# analog_in.net
KiCad netlist of a schematic drawn in Altium Designer
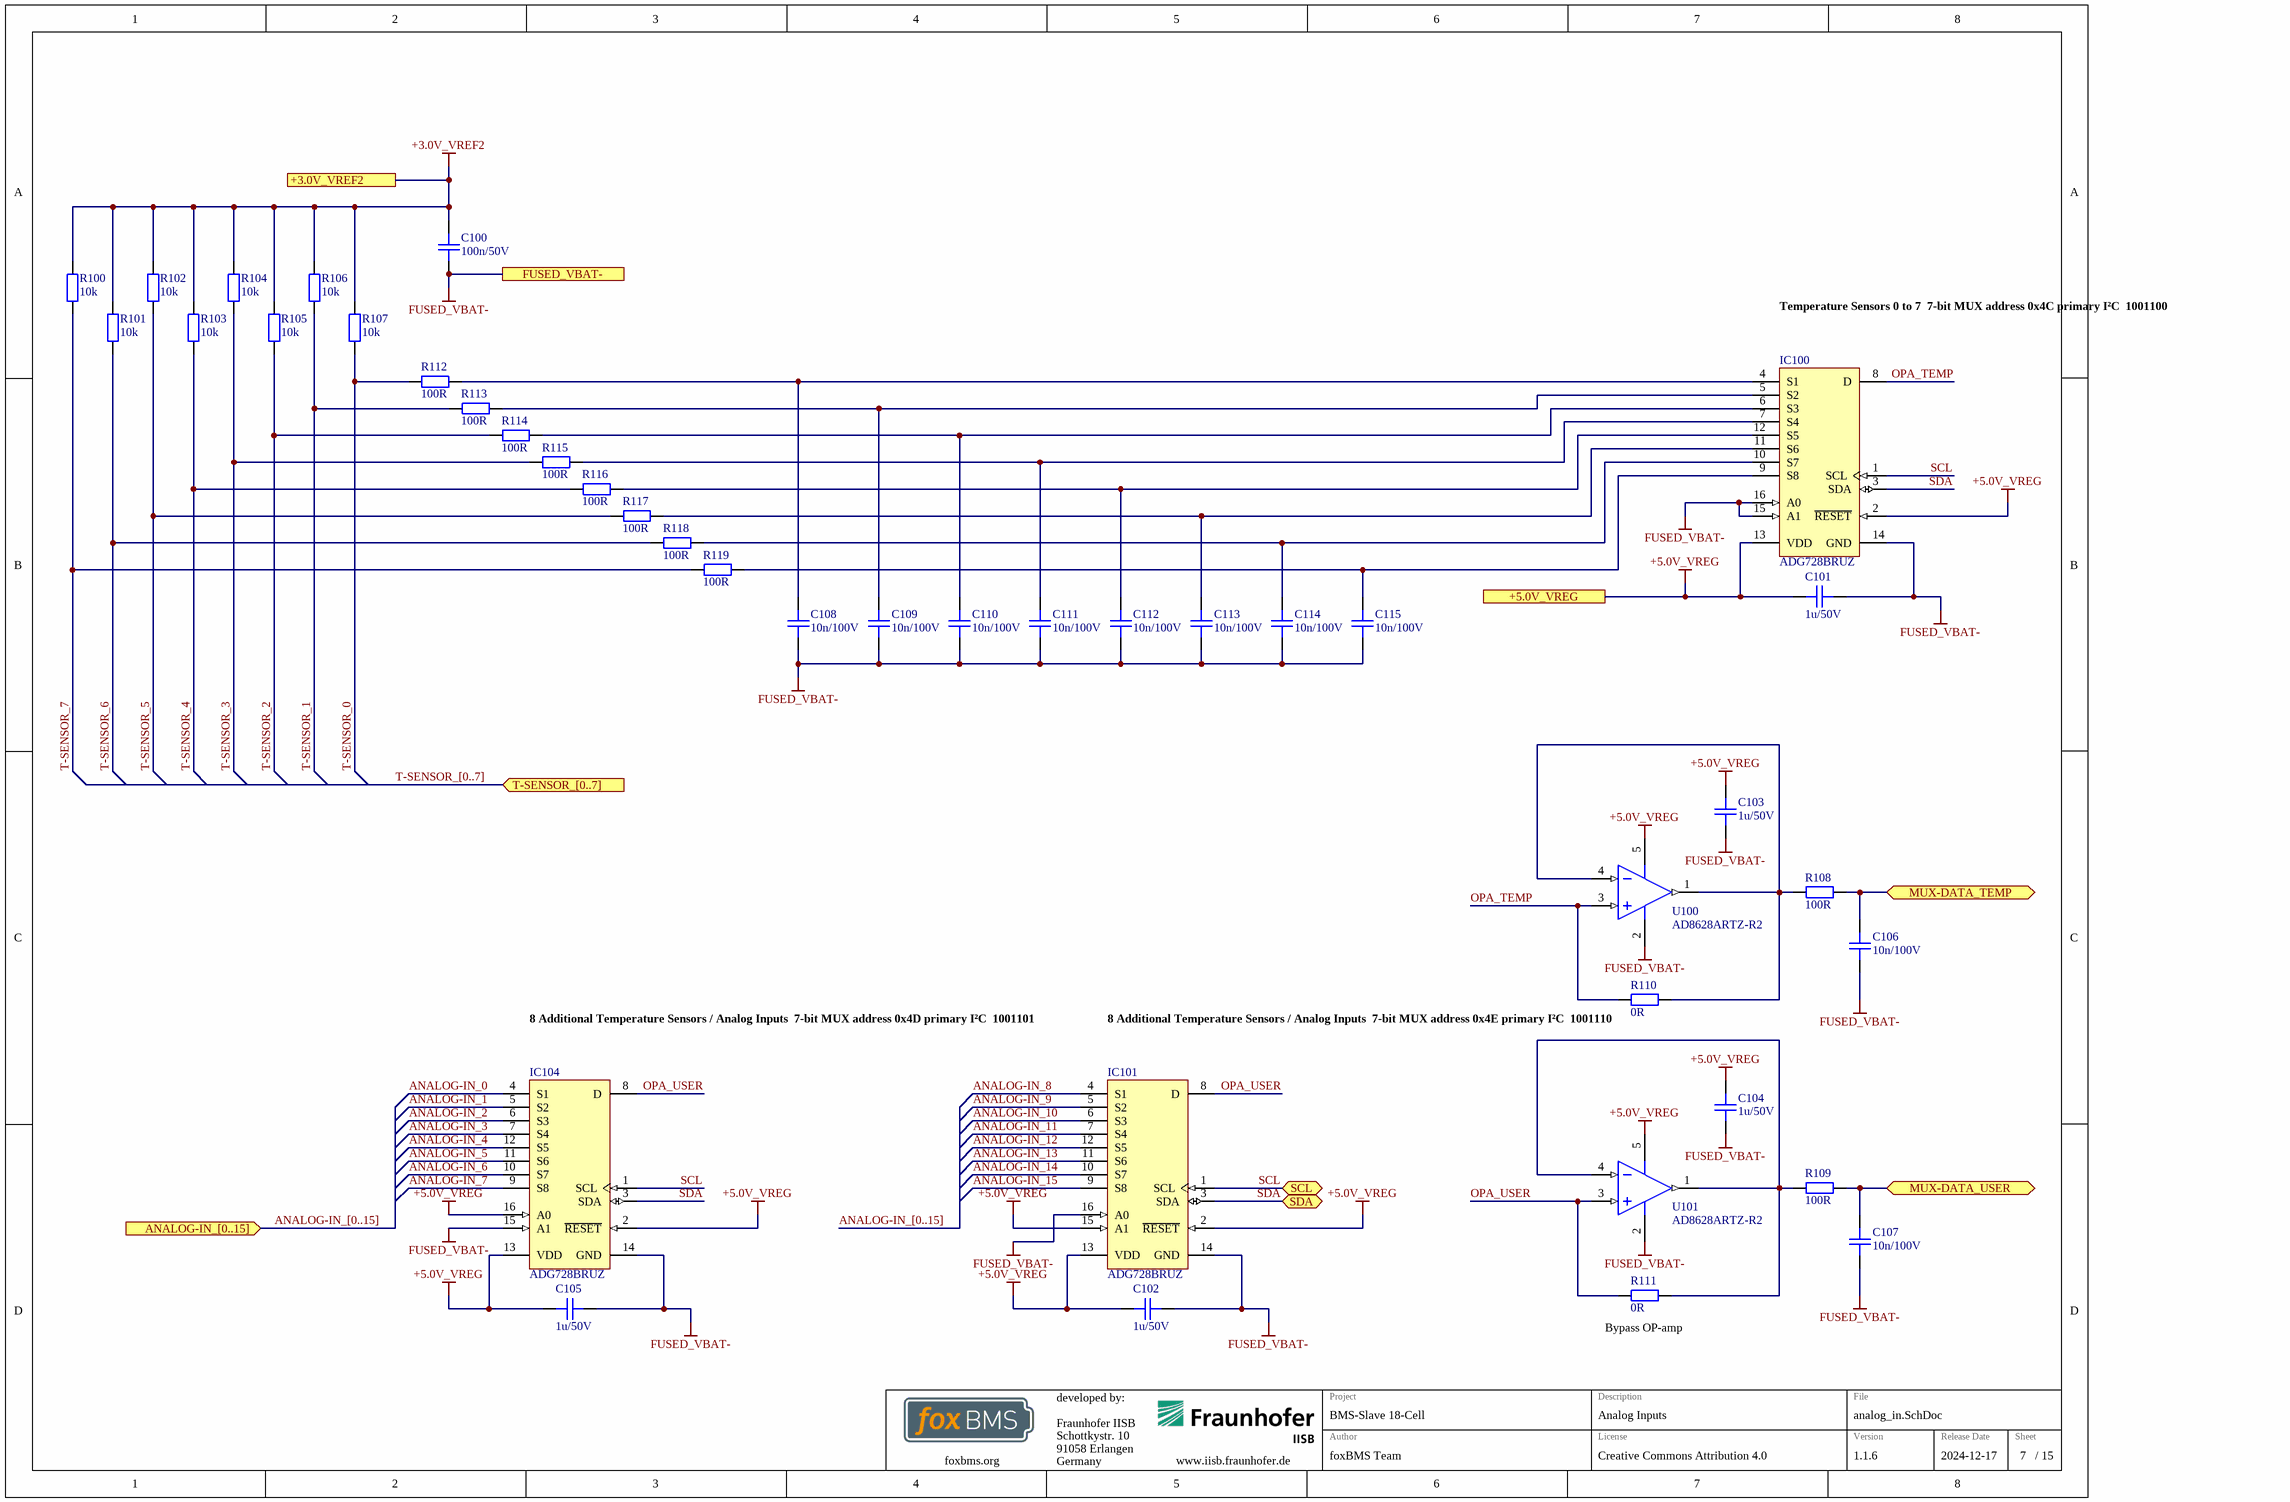
[diagram p0: analog_in.SchDoc]

(export (version "E")
  (design (tool "Eeschema 10.0.6"))
  (components
    (comp (ref "C100")
      (value "100n/50V")
      (footprint "CAPC1608X08N")
      (description "MLCC")
      (fields (field (name "PART NUMBER") "gen_C_ceramic_100n_50V_X7R_0603"))
      (libsource (lib "OE750") (part "C"))
    )
    (comp (ref "C101")
      (value "1u/50V")
      (footprint "CAPC2012X14N")
      (description "MLCC")
      (fields (field (name "PART NUMBER") "gen_C_ceramic_1u_50V_X7R_0805") (field (name "TOLERANCE") "± 10%"))
      (libsource (lib "OE750") (part "C"))
    )
    (comp (ref "C102")
      (value "1u/50V")
      (footprint "CAPC2012X14N")
      (description "MLCC")
      (fields (field (name "PART NUMBER") "gen_C_ceramic_1u_50V_X7R_0805") (field (name "TOLERANCE") "± 10%"))
      (libsource (lib "OE750") (part "C"))
    )
    (comp (ref "C103")
      (value "1u/50V")
      (footprint "CAPC2012X14N")
      (description "MLCC")
      (fields (field (name "PART NUMBER") "gen_C_ceramic_1u_50V_X7R_0805") (field (name "TOLERANCE") "± 10%"))
      (libsource (lib "OE750") (part "C"))
    )
    (comp (ref "C104")
      (value "1u/50V")
      (footprint "CAPC2012X14N")
      (description "MLCC")
      (fields (field (name "PART NUMBER") "gen_C_ceramic_1u_50V_X7R_0805") (field (name "TOLERANCE") "± 10%"))
      (libsource (lib "OE750") (part "C"))
    )
    (comp (ref "C105")
      (value "1u/50V")
      (footprint "CAPC2012X14N")
      (description "MLCC")
      (fields (field (name "PART NUMBER") "gen_C_ceramic_1u_50V_X7R_0805") (field (name "TOLERANCE") "± 10%"))
      (libsource (lib "OE750") (part "C"))
    )
    (comp (ref "C106")
      (value "10n/100V")
      (footprint "CAPC1608X08N")
      (description "MLCC")
      (fields (field (name "PART NUMBER") "gen_C_ceramic_10n_100V_X7R_0603"))
      (libsource (lib "OE750") (part "C"))
    )
    (comp (ref "C107")
      (value "10n/100V")
      (footprint "CAPC1608X08N")
      (description "MLCC")
      (fields (field (name "PART NUMBER") "gen_C_ceramic_10n_100V_X7R_0603"))
      (libsource (lib "OE750") (part "C"))
    )
    (comp (ref "C108")
      (value "10n/100V")
      (footprint "CAPC1608X08N")
      (description "MLCC")
      (fields (field (name "PART NUMBER") "gen_C_ceramic_10n_100V_X7R_0603"))
      (libsource (lib "OE750") (part "C"))
    )
    (comp (ref "C109")
      (value "10n/100V")
      (footprint "CAPC1608X08N")
      (description "MLCC")
      (fields (field (name "PART NUMBER") "gen_C_ceramic_10n_100V_X7R_0603"))
      (libsource (lib "OE750") (part "C"))
    )
    (comp (ref "C110")
      (value "10n/100V")
      (footprint "CAPC1608X08N")
      (description "MLCC")
      (fields (field (name "PART NUMBER") "gen_C_ceramic_10n_100V_X7R_0603"))
      (libsource (lib "OE750") (part "C"))
    )
    (comp (ref "C111")
      (value "10n/100V")
      (footprint "CAPC1608X08N")
      (description "MLCC")
      (fields (field (name "PART NUMBER") "gen_C_ceramic_10n_100V_X7R_0603"))
      (libsource (lib "OE750") (part "C"))
    )
    (comp (ref "C112")
      (value "10n/100V")
      (footprint "CAPC1608X08N")
      (description "MLCC")
      (fields (field (name "PART NUMBER") "gen_C_ceramic_10n_100V_X7R_0603"))
      (libsource (lib "OE750") (part "C"))
    )
    (comp (ref "C113")
      (value "10n/100V")
      (footprint "CAPC1608X08N")
      (description "MLCC")
      (fields (field (name "PART NUMBER") "gen_C_ceramic_10n_100V_X7R_0603"))
      (libsource (lib "OE750") (part "C"))
    )
    (comp (ref "C114")
      (value "10n/100V")
      (footprint "CAPC1608X08N")
      (description "MLCC")
      (fields (field (name "PART NUMBER") "gen_C_ceramic_10n_100V_X7R_0603"))
      (libsource (lib "OE750") (part "C"))
    )
    (comp (ref "C115")
      (value "10n/100V")
      (footprint "CAPC1608X08N")
      (description "MLCC")
      (fields (field (name "PART NUMBER") "gen_C_ceramic_10n_100V_X7R_0603"))
      (libsource (lib "OE750") (part "C"))
    )
    (comp (ref "IC100")
      (value "ADG728BRUZ")
      (footprint "ADI-RU-16_M")
      (fields (field (name "MANUFACTURER") "Analog Devices"))
      (libsource (lib "Altium Content Vault") (part "ADI-ADG728-RU-16"))
    )
    (comp (ref "IC101")
      (value "ADG728BRUZ")
      (footprint "ADI-RU-16_M")
      (fields (field (name "MANUFACTURER") "Analog Devices"))
      (libsource (lib "Altium Content Vault") (part "ADI-ADG728-RU-16"))
    )
    (comp (ref "IC104")
      (value "ADG728BRUZ")
      (footprint "ADI-RU-16_M")
      (fields (field (name "MANUFACTURER") "Analog Devices"))
      (libsource (lib "Altium Content Vault") (part "ADI-ADG728-RU-16"))
    )
    (comp (ref "R100")
      (value "10k")
      (footprint "RESC1608X05N")
      (description "SMD Resistor 10k 0603")
      (fields (field (name "PART NUMBER") "gen_R_10k_0603") (field (name "TOLERANCE") "1%"))
      (libsource (lib "OE750") (part "R"))
    )
    (comp (ref "R101")
      (value "10k")
      (footprint "RESC1608X05N")
      (description "SMD Resistor 10k 0603")
      (fields (field (name "PART NUMBER") "gen_R_10k_0603") (field (name "TOLERANCE") "1%"))
      (libsource (lib "OE750") (part "R"))
    )
    (comp (ref "R102")
      (value "10k")
      (footprint "RESC1608X05N")
      (description "SMD Resistor 10k 0603")
      (fields (field (name "PART NUMBER") "gen_R_10k_0603") (field (name "TOLERANCE") "1%"))
      (libsource (lib "OE750") (part "R"))
    )
    (comp (ref "R103")
      (value "10k")
      (footprint "RESC1608X05N")
      (description "SMD Resistor 10k 0603")
      (fields (field (name "PART NUMBER") "gen_R_10k_0603") (field (name "TOLERANCE") "1%"))
      (libsource (lib "OE750") (part "R"))
    )
    (comp (ref "R104")
      (value "10k")
      (footprint "RESC1608X05N")
      (description "SMD Resistor 10k 0603")
      (fields (field (name "PART NUMBER") "gen_R_10k_0603") (field (name "TOLERANCE") "1%"))
      (libsource (lib "OE750") (part "R"))
    )
    (comp (ref "R105")
      (value "10k")
      (footprint "RESC1608X05N")
      (description "SMD Resistor 10k 0603")
      (fields (field (name "PART NUMBER") "gen_R_10k_0603") (field (name "TOLERANCE") "1%"))
      (libsource (lib "OE750") (part "R"))
    )
    (comp (ref "R106")
      (value "10k")
      (footprint "RESC1608X05N")
      (description "SMD Resistor 10k 0603")
      (fields (field (name "PART NUMBER") "gen_R_10k_0603") (field (name "TOLERANCE") "1%"))
      (libsource (lib "OE750") (part "R"))
    )
    (comp (ref "R107")
      (value "10k")
      (footprint "RESC1608X05N")
      (description "SMD Resistor 10k 0603")
      (fields (field (name "PART NUMBER") "gen_R_10k_0603") (field (name "TOLERANCE") "1%"))
      (libsource (lib "OE750") (part "R"))
    )
    (comp (ref "R108")
      (value "100R")
      (footprint "RESC1608X05N")
      (description "SMD Resistor 100R 0603")
      (fields (field (name "PART NUMBER") "gen_R_100R_0603") (field (name "TOLERANCE") "1%"))
      (libsource (lib "OE750") (part "R"))
    )
    (comp (ref "R109")
      (value "100R")
      (footprint "RESC1608X05N")
      (description "SMD Resistor 100R 0603")
      (fields (field (name "PART NUMBER") "gen_R_100R_0603") (field (name "TOLERANCE") "1%"))
      (libsource (lib "OE750") (part "R"))
    )
    (comp (ref "R110")
      (value "0R")
      (footprint "RESC1608X05N")
      (description "SMD Resistor 0R 0603")
      (fields (field (name "PART NUMBER") "gen_R_0R_0603") (field (name "POWER") "0.1W"))
      (libsource (lib "OE750") (part "R"))
    )
    (comp (ref "R111")
      (value "0R")
      (footprint "RESC1608X05N")
      (description "SMD Resistor 0R 0603")
      (fields (field (name "PART NUMBER") "gen_R_0R_0603") (field (name "POWER") "0.1W"))
      (libsource (lib "OE750") (part "R"))
    )
    (comp (ref "R112")
      (value "100R")
      (footprint "RESC1608X05N")
      (description "SMD Resistor 100R 0603")
      (fields (field (name "PART NUMBER") "gen_R_100R_0603") (field (name "TOLERANCE") "1%"))
      (libsource (lib "OE750") (part "R"))
    )
    (comp (ref "R113")
      (value "100R")
      (footprint "RESC1608X05N")
      (description "SMD Resistor 100R 0603")
      (fields (field (name "PART NUMBER") "gen_R_100R_0603") (field (name "TOLERANCE") "1%"))
      (libsource (lib "OE750") (part "R"))
    )
    (comp (ref "R114")
      (value "100R")
      (footprint "RESC1608X05N")
      (description "SMD Resistor 100R 0603")
      (fields (field (name "PART NUMBER") "gen_R_100R_0603") (field (name "TOLERANCE") "1%"))
      (libsource (lib "OE750") (part "R"))
    )
    (comp (ref "R115")
      (value "100R")
      (footprint "RESC1608X05N")
      (description "SMD Resistor 100R 0603")
      (fields (field (name "PART NUMBER") "gen_R_100R_0603") (field (name "TOLERANCE") "1%"))
      (libsource (lib "OE750") (part "R"))
    )
    (comp (ref "R116")
      (value "100R")
      (footprint "RESC1608X05N")
      (description "SMD Resistor 100R 0603")
      (fields (field (name "PART NUMBER") "gen_R_100R_0603") (field (name "TOLERANCE") "1%"))
      (libsource (lib "OE750") (part "R"))
    )
    (comp (ref "R117")
      (value "100R")
      (footprint "RESC1608X05N")
      (description "SMD Resistor 100R 0603")
      (fields (field (name "PART NUMBER") "gen_R_100R_0603") (field (name "TOLERANCE") "1%"))
      (libsource (lib "OE750") (part "R"))
    )
    (comp (ref "R118")
      (value "100R")
      (footprint "RESC1608X05N")
      (description "SMD Resistor 100R 0603")
      (fields (field (name "PART NUMBER") "gen_R_100R_0603") (field (name "TOLERANCE") "1%"))
      (libsource (lib "OE750") (part "R"))
    )
    (comp (ref "R119")
      (value "100R")
      (footprint "RESC1608X05N")
      (description "SMD Resistor 100R 0603")
      (fields (field (name "PART NUMBER") "gen_R_100R_0603") (field (name "TOLERANCE") "1%"))
      (libsource (lib "OE750") (part "R"))
    )
    (comp (ref "U100")
      (value "AD8628ARTZ-R2")
      (footprint "ADI-RJ-5_M")
      (fields (field (name "MANUFACTURER") "Analog Devices") (field (name "GENERIC PART NUMBER") "AD8628"))
      (libsource (lib "Altium Content Vault") (part "ADI-ADxxxx-X-5"))
    )
    (comp (ref "U101")
      (value "AD8628ARTZ-R2")
      (footprint "ADI-RJ-5_M")
      (fields (field (name "MANUFACTURER") "Analog Devices") (field (name "GENERIC PART NUMBER") "AD8628"))
      (libsource (lib "Altium Content Vault") (part "ADI-ADxxxx-X-5"))
    )
  )
  (nets
    (net (code "1") (name "+3.0V_VREF2") (class "Default")
      (node (ref "C100") (pin "2") (pinfunction "2_2") (pintype "passive"))
      (node (ref "R100") (pin "2") (pinfunction "2_2") (pintype "passive"))
      (node (ref "R101") (pin "2") (pinfunction "2_2") (pintype "passive"))
      (node (ref "R102") (pin "2") (pinfunction "2_2") (pintype "passive"))
      (node (ref "R103") (pin "2") (pinfunction "2_2") (pintype "passive"))
      (node (ref "R104") (pin "2") (pinfunction "2_2") (pintype "passive"))
      (node (ref "R105") (pin "2") (pinfunction "2_2") (pintype "passive"))
      (node (ref "R106") (pin "2") (pinfunction "2_2") (pintype "passive"))
      (node (ref "R107") (pin "2") (pinfunction "2_2") (pintype "passive"))
    )
    (net (code "2") (name "+5.0V_VREG") (class "Default")
      (node (ref "C101") (pin "2") (pinfunction "2_2") (pintype "passive"))
      (node (ref "C102") (pin "2") (pinfunction "2_2") (pintype "passive"))
      (node (ref "C103") (pin "2") (pinfunction "2_2") (pintype "passive"))
      (node (ref "C104") (pin "2") (pinfunction "2_2") (pintype "passive"))
      (node (ref "C105") (pin "2") (pinfunction "2_2") (pintype "passive"))
      (node (ref "IC100") (pin "13") (pinfunction "VDD_13") (pintype "power_in"))
      (node (ref "IC100") (pin "2") (pinfunction "~{RESET}_2") (pintype "input"))
      (node (ref "IC101") (pin "13") (pinfunction "VDD_13") (pintype "power_in"))
      (node (ref "IC101") (pin "15") (pinfunction "A1_15") (pintype "input"))
      (node (ref "IC101") (pin "2") (pinfunction "~{RESET}_2") (pintype "input"))
      (node (ref "IC104") (pin "13") (pinfunction "VDD_13") (pintype "power_in"))
      (node (ref "IC104") (pin "16") (pinfunction "A0_16") (pintype "input"))
      (node (ref "IC104") (pin "2") (pinfunction "~{RESET}_2") (pintype "input"))
      (node (ref "U100") (pin "5") (pinfunction "+V_5") (pintype "power_in"))
      (node (ref "U101") (pin "5") (pinfunction "+V_5") (pintype "power_in"))
    )
    (net (code "3") (name "/ANALOG-IN_0") (class "Default")
      (node (ref "IC104") (pin "4") (pinfunction "S1_4") (pintype "passive"))
    )
    (net (code "4") (name "/ANALOG-IN_1") (class "Default")
      (node (ref "IC104") (pin "5") (pinfunction "S2_5") (pintype "passive"))
    )
    (net (code "5") (name "/ANALOG-IN_2") (class "Default")
      (node (ref "IC104") (pin "6") (pinfunction "S3_6") (pintype "passive"))
    )
    (net (code "6") (name "/ANALOG-IN_3") (class "Default")
      (node (ref "IC104") (pin "7") (pinfunction "S4_7") (pintype "passive"))
    )
    (net (code "7") (name "/ANALOG-IN_4") (class "Default")
      (node (ref "IC104") (pin "12") (pinfunction "S5_12") (pintype "passive"))
    )
    (net (code "8") (name "/ANALOG-IN_5") (class "Default")
      (node (ref "IC104") (pin "11") (pinfunction "S6_11") (pintype "passive"))
    )
    (net (code "9") (name "/ANALOG-IN_6") (class "Default")
      (node (ref "IC104") (pin "10") (pinfunction "S7_10") (pintype "passive"))
    )
    (net (code "10") (name "/ANALOG-IN_7") (class "Default")
      (node (ref "IC104") (pin "9") (pinfunction "S8_9") (pintype "passive"))
    )
    (net (code "11") (name "/ANALOG-IN_8") (class "Default")
      (node (ref "IC101") (pin "4") (pinfunction "S1_4") (pintype "passive"))
    )
    (net (code "12") (name "/ANALOG-IN_9") (class "Default")
      (node (ref "IC101") (pin "5") (pinfunction "S2_5") (pintype "passive"))
    )
    (net (code "13") (name "/ANALOG-IN_10") (class "Default")
      (node (ref "IC101") (pin "6") (pinfunction "S3_6") (pintype "passive"))
    )
    (net (code "14") (name "/ANALOG-IN_11") (class "Default")
      (node (ref "IC101") (pin "7") (pinfunction "S4_7") (pintype "passive"))
    )
    (net (code "15") (name "/ANALOG-IN_12") (class "Default")
      (node (ref "IC101") (pin "12") (pinfunction "S5_12") (pintype "passive"))
    )
    (net (code "16") (name "/ANALOG-IN_13") (class "Default")
      (node (ref "IC101") (pin "11") (pinfunction "S6_11") (pintype "passive"))
    )
    (net (code "17") (name "/ANALOG-IN_14") (class "Default")
      (node (ref "IC101") (pin "10") (pinfunction "S7_10") (pintype "passive"))
    )
    (net (code "18") (name "/ANALOG-IN_15") (class "Default")
      (node (ref "IC101") (pin "9") (pinfunction "S8_9") (pintype "passive"))
    )
    (net (code "20") (name "/MUX-DATA_TEMP") (class "Default")
      (node (ref "C106") (pin "2") (pinfunction "2_2") (pintype "passive"))
      (node (ref "R108") (pin "2") (pinfunction "2_2") (pintype "passive"))
    )
    (net (code "21") (name "/MUX-DATA_USER") (class "Default")
      (node (ref "C107") (pin "2") (pinfunction "2_2") (pintype "passive"))
      (node (ref "R109") (pin "2") (pinfunction "2_2") (pintype "passive"))
    )
    (net (code "22") (name "/OPA_TEMP") (class "Default")
      (node (ref "IC100") (pin "8") (pinfunction "D_8") (pintype "passive"))
      (node (ref "R110") (pin "1") (pinfunction "1_1") (pintype "passive"))
      (node (ref "U100") (pin "3") (pinfunction "+IN_3") (pintype "input"))
    )
    (net (code "23") (name "/OPA_USER") (class "Default")
      (node (ref "IC101") (pin "8") (pinfunction "D_8") (pintype "passive"))
      (node (ref "IC104") (pin "8") (pinfunction "D_8") (pintype "passive"))
      (node (ref "R111") (pin "1") (pinfunction "1_1") (pintype "passive"))
      (node (ref "U101") (pin "3") (pinfunction "+IN_3") (pintype "input"))
    )
    (net (code "24") (name "/SCL") (class "Default")
      (node (ref "IC100") (pin "1") (pinfunction "SCL_1") (pintype "input"))
      (node (ref "IC101") (pin "1") (pinfunction "SCL_1") (pintype "input"))
      (node (ref "IC104") (pin "1") (pinfunction "SCL_1") (pintype "input"))
    )
    (net (code "25") (name "/SDA") (class "Default")
      (node (ref "IC100") (pin "3") (pinfunction "SDA_3") (pintype "bidirectional"))
      (node (ref "IC101") (pin "3") (pinfunction "SDA_3") (pintype "bidirectional"))
      (node (ref "IC104") (pin "3") (pinfunction "SDA_3") (pintype "bidirectional"))
    )
    (net (code "26") (name "/T-SENSOR_0") (class "Default")
      (node (ref "R107") (pin "1") (pinfunction "1_1") (pintype "passive"))
      (node (ref "R112") (pin "2") (pinfunction "2_2") (pintype "passive"))
    )
    (net (code "27") (name "/T-SENSOR_1") (class "Default")
      (node (ref "R106") (pin "1") (pinfunction "1_1") (pintype "passive"))
      (node (ref "R113") (pin "2") (pinfunction "2_2") (pintype "passive"))
    )
    (net (code "28") (name "/T-SENSOR_2") (class "Default")
      (node (ref "R105") (pin "1") (pinfunction "1_1") (pintype "passive"))
      (node (ref "R114") (pin "2") (pinfunction "2_2") (pintype "passive"))
    )
    (net (code "29") (name "/T-SENSOR_3") (class "Default")
      (node (ref "R104") (pin "1") (pinfunction "1_1") (pintype "passive"))
      (node (ref "R115") (pin "2") (pinfunction "2_2") (pintype "passive"))
    )
    (net (code "30") (name "/T-SENSOR_4") (class "Default")
      (node (ref "R103") (pin "1") (pinfunction "1_1") (pintype "passive"))
      (node (ref "R116") (pin "2") (pinfunction "2_2") (pintype "passive"))
    )
    (net (code "31") (name "/T-SENSOR_5") (class "Default")
      (node (ref "R102") (pin "1") (pinfunction "1_1") (pintype "passive"))
      (node (ref "R117") (pin "2") (pinfunction "2_2") (pintype "passive"))
    )
    (net (code "32") (name "/T-SENSOR_6") (class "Default")
      (node (ref "R101") (pin "1") (pinfunction "1_1") (pintype "passive"))
      (node (ref "R118") (pin "2") (pinfunction "2_2") (pintype "passive"))
    )
    (net (code "33") (name "/T-SENSOR_7") (class "Default")
      (node (ref "R100") (pin "1") (pinfunction "1_1") (pintype "passive"))
      (node (ref "R119") (pin "2") (pinfunction "2_2") (pintype "passive"))
    )
    (net (code "35") (name "FUSED_VBAT-") (class "Default")
      (node (ref "C100") (pin "1") (pinfunction "1_1") (pintype "passive"))
      (node (ref "C101") (pin "1") (pinfunction "1_1") (pintype "passive"))
      (node (ref "C102") (pin "1") (pinfunction "1_1") (pintype "passive"))
      (node (ref "C103") (pin "1") (pinfunction "1_1") (pintype "passive"))
      (node (ref "C104") (pin "1") (pinfunction "1_1") (pintype "passive"))
      (node (ref "C105") (pin "1") (pinfunction "1_1") (pintype "passive"))
      (node (ref "C106") (pin "1") (pinfunction "1_1") (pintype "passive"))
      (node (ref "C107") (pin "1") (pinfunction "1_1") (pintype "passive"))
      (node (ref "C108") (pin "1") (pinfunction "1_1") (pintype "passive"))
      (node (ref "C109") (pin "1") (pinfunction "1_1") (pintype "passive"))
      (node (ref "C110") (pin "1") (pinfunction "1_1") (pintype "passive"))
      (node (ref "C111") (pin "1") (pinfunction "1_1") (pintype "passive"))
      (node (ref "C112") (pin "1") (pinfunction "1_1") (pintype "passive"))
      (node (ref "C113") (pin "1") (pinfunction "1_1") (pintype "passive"))
      (node (ref "C114") (pin "1") (pinfunction "1_1") (pintype "passive"))
      (node (ref "C115") (pin "1") (pinfunction "1_1") (pintype "passive"))
      (node (ref "IC100") (pin "14") (pinfunction "GND_14") (pintype "power_in"))
      (node (ref "IC100") (pin "15") (pinfunction "A1_15") (pintype "input"))
      (node (ref "IC100") (pin "16") (pinfunction "A0_16") (pintype "input"))
      (node (ref "IC101") (pin "14") (pinfunction "GND_14") (pintype "power_in"))
      (node (ref "IC101") (pin "16") (pinfunction "A0_16") (pintype "input"))
      (node (ref "IC104") (pin "14") (pinfunction "GND_14") (pintype "power_in"))
      (node (ref "IC104") (pin "15") (pinfunction "A1_15") (pintype "input"))
      (node (ref "U100") (pin "2") (pinfunction "-V_2") (pintype "power_in"))
      (node (ref "U101") (pin "2") (pinfunction "-V_2") (pintype "power_in"))
    )
    (net (code "36") (name "Net-(IC100-S1)") (class "Default")
      (node (ref "C108") (pin "2") (pinfunction "2_2") (pintype "passive"))
      (node (ref "IC100") (pin "4") (pinfunction "S1_4") (pintype "passive"))
      (node (ref "R112") (pin "1") (pinfunction "1_1") (pintype "passive"))
    )
    (net (code "37") (name "Net-(IC100-S2)") (class "Default")
      (node (ref "C109") (pin "2") (pinfunction "2_2") (pintype "passive"))
      (node (ref "IC100") (pin "5") (pinfunction "S2_5") (pintype "passive"))
      (node (ref "R113") (pin "1") (pinfunction "1_1") (pintype "passive"))
    )
    (net (code "38") (name "Net-(IC100-S3)") (class "Default")
      (node (ref "C110") (pin "2") (pinfunction "2_2") (pintype "passive"))
      (node (ref "IC100") (pin "6") (pinfunction "S3_6") (pintype "passive"))
      (node (ref "R114") (pin "1") (pinfunction "1_1") (pintype "passive"))
    )
    (net (code "39") (name "Net-(IC100-S4)") (class "Default")
      (node (ref "C111") (pin "2") (pinfunction "2_2") (pintype "passive"))
      (node (ref "IC100") (pin "7") (pinfunction "S4_7") (pintype "passive"))
      (node (ref "R115") (pin "1") (pinfunction "1_1") (pintype "passive"))
    )
    (net (code "40") (name "Net-(IC100-S5)") (class "Default")
      (node (ref "C112") (pin "2") (pinfunction "2_2") (pintype "passive"))
      (node (ref "IC100") (pin "12") (pinfunction "S5_12") (pintype "passive"))
      (node (ref "R116") (pin "1") (pinfunction "1_1") (pintype "passive"))
    )
    (net (code "41") (name "Net-(IC100-S6)") (class "Default")
      (node (ref "C113") (pin "2") (pinfunction "2_2") (pintype "passive"))
      (node (ref "IC100") (pin "11") (pinfunction "S6_11") (pintype "passive"))
      (node (ref "R117") (pin "1") (pinfunction "1_1") (pintype "passive"))
    )
    (net (code "42") (name "Net-(IC100-S7)") (class "Default")
      (node (ref "C114") (pin "2") (pinfunction "2_2") (pintype "passive"))
      (node (ref "IC100") (pin "10") (pinfunction "S7_10") (pintype "passive"))
      (node (ref "R118") (pin "1") (pinfunction "1_1") (pintype "passive"))
    )
    (net (code "43") (name "Net-(IC100-S8)") (class "Default")
      (node (ref "C115") (pin "2") (pinfunction "2_2") (pintype "passive"))
      (node (ref "IC100") (pin "9") (pinfunction "S8_9") (pintype "passive"))
      (node (ref "R119") (pin "1") (pinfunction "1_1") (pintype "passive"))
    )
    (net (code "44") (name "Net-(U100--IN)") (class "Default")
      (node (ref "R108") (pin "1") (pinfunction "1_1") (pintype "passive"))
      (node (ref "R110") (pin "2") (pinfunction "2_2") (pintype "passive"))
      (node (ref "U100") (pin "1") (pinfunction "OUT_1") (pintype "output"))
      (node (ref "U100") (pin "4") (pinfunction "-IN_4") (pintype "input"))
    )
    (net (code "45") (name "Net-(U101--IN)") (class "Default")
      (node (ref "R109") (pin "1") (pinfunction "1_1") (pintype "passive"))
      (node (ref "R111") (pin "2") (pinfunction "2_2") (pintype "passive"))
      (node (ref "U101") (pin "1") (pinfunction "OUT_1") (pintype "output"))
      (node (ref "U101") (pin "4") (pinfunction "-IN_4") (pintype "input"))
    )
  )
)
